# mattduino_mvp.net
KiCad netlist of a schematic drawn in EAGLE
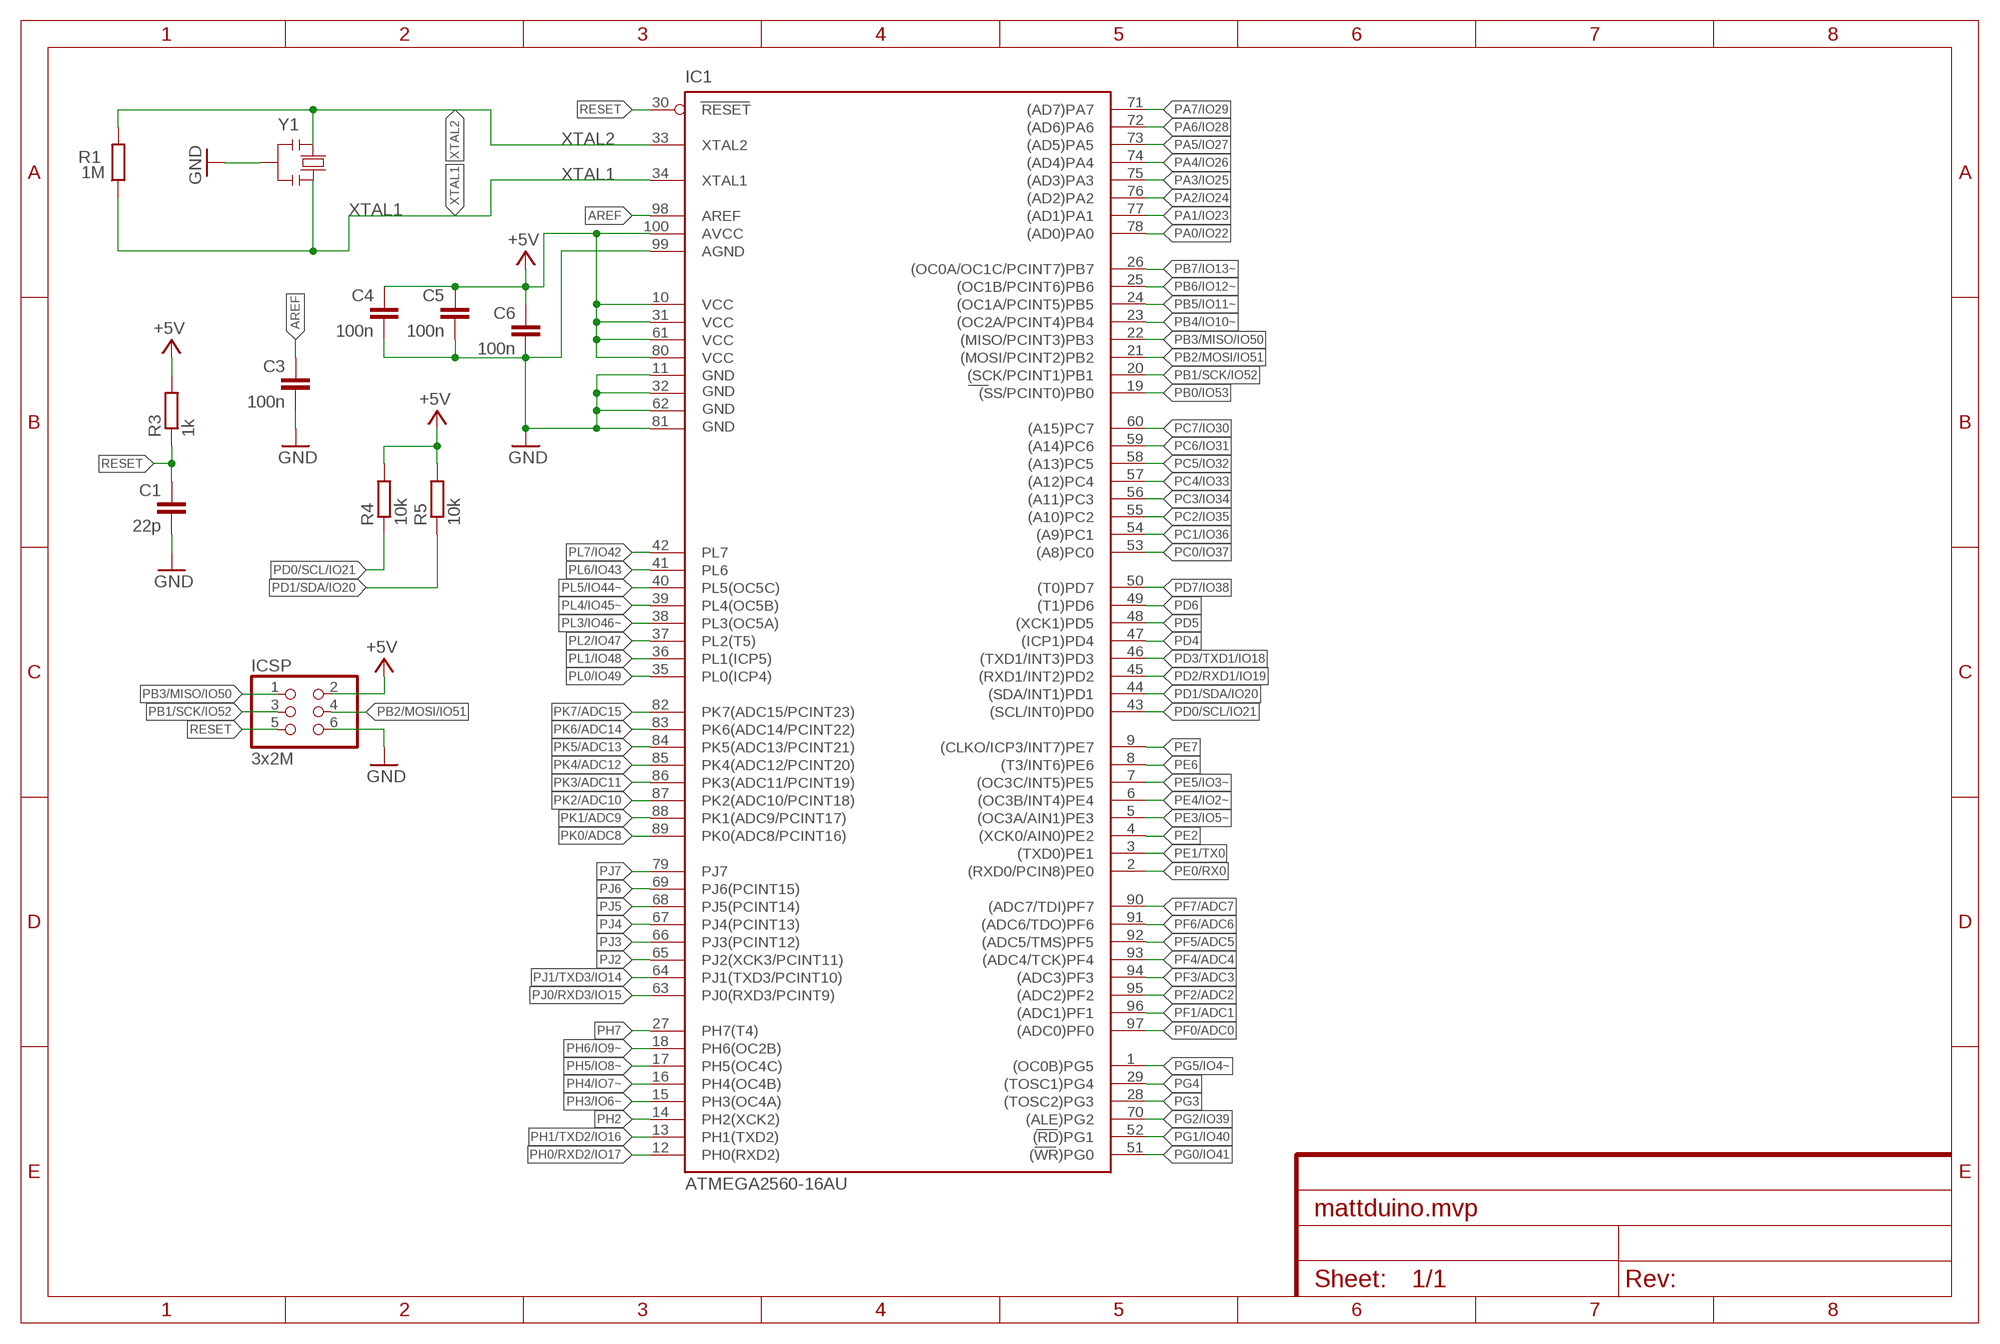
[diagram p0: schematic, sheet 1]

(export (version "E")
  (design (tool "Eeschema 10.0.6"))
  (components
    (comp (ref "C1")
      (value "22p")
      (footprint "eagle-import:C1206")
      (libsource (lib "eagle-import") (part "C-EUC1206"))
    )
    (comp (ref "C3")
      (value "100n")
      (footprint "eagle-import:C1206")
      (libsource (lib "eagle-import") (part "C-EUC1206"))
    )
    (comp (ref "C4")
      (value "100n")
      (footprint "eagle-import:C1206")
      (libsource (lib "eagle-import") (part "C-EUC1206"))
    )
    (comp (ref "C5")
      (value "100n")
      (footprint "eagle-import:C1206")
      (libsource (lib "eagle-import") (part "C-EUC1206"))
    )
    (comp (ref "C6")
      (value "100n")
      (footprint "eagle-import:C1206")
      (libsource (lib "eagle-import") (part "C-EUC1206"))
    )
    (comp (ref "IC1")
      (value "ATMEGA2560-16AU")
      (footprint "eagle-import:TQFP100")
      (libsource (lib "eagle-import") (part "ATMEGA2560AU2560-16"))
    )
    (comp (ref "ICSP")
      (value "3x2M")
      (footprint "eagle-import:2X03")
      (libsource (lib "eagle-import") (part "PINHD-2X3"))
    )
    (comp (ref "R1")
      (value "1M")
      (footprint "eagle-import:R1206")
      (libsource (lib "eagle-import") (part "R-EU_R1206"))
    )
    (comp (ref "R3")
      (value "1k")
      (footprint "eagle-import:R1206")
      (libsource (lib "eagle-import") (part "R-EU_R1206"))
    )
    (comp (ref "R4")
      (value "10k")
      (footprint "eagle-import:R1206")
      (libsource (lib "eagle-import") (part "R-EU_R1206"))
    )
    (comp (ref "R5")
      (value "10k")
      (footprint "eagle-import:R1206")
      (libsource (lib "eagle-import") (part "R-EU_R1206"))
    )
    (comp (ref "Y1")
      (value "CSTCE16M0V53-R0 16MHZ")
      (footprint "eagle-import:RESONATOR")
      (libsource (lib "eagle-import") (part "RESONATORMU"))
    )
  )
  (nets
    (net (code "1") (name "+5V") (class "Default")
      (node (ref "C4") (pin "1") (pinfunction "1_1") (pintype "passive"))
      (node (ref "C5") (pin "1") (pinfunction "1_1") (pintype "passive"))
      (node (ref "C6") (pin "1") (pinfunction "1_1") (pintype "passive"))
      (node (ref "IC1") (pin "10") (pinfunction "VCC_10") (pintype "power_in"))
      (node (ref "IC1") (pin "100") (pinfunction "AVCC_100") (pintype "power_in"))
      (node (ref "IC1") (pin "31") (pinfunction "VCC1_31") (pintype "power_in"))
      (node (ref "IC1") (pin "61") (pinfunction "VCC2_61") (pintype "power_in"))
      (node (ref "IC1") (pin "80") (pinfunction "VCC3_80") (pintype "power_in"))
      (node (ref "ICSP") (pin "2") (pinfunction "2_2") (pintype "passive"))
      (node (ref "R3") (pin "2") (pinfunction "2_2") (pintype "passive"))
      (node (ref "R4") (pin "2") (pinfunction "2_2") (pintype "passive"))
      (node (ref "R5") (pin "2") (pinfunction "2_2") (pintype "passive"))
    )
    (net (code "2") (name "/PB4{slash}IO10~{}") (class "Default")
      (node (ref "IC1") (pin "23") (pinfunction "(OC2A/PCINT4)PB4_23") (pintype "bidirectional"))
    )
    (net (code "3") (name "/PB5{slash}IO11~{}") (class "Default")
      (node (ref "IC1") (pin "24") (pinfunction "(OC1A/PCINT5)PB5_24") (pintype "bidirectional"))
    )
    (net (code "4") (name "/PB6{slash}IO12~{}") (class "Default")
      (node (ref "IC1") (pin "25") (pinfunction "(OC1B/PCINT6)PB6_25") (pintype "bidirectional"))
    )
    (net (code "5") (name "/PB7{slash}IO13~{}") (class "Default")
      (node (ref "IC1") (pin "26") (pinfunction "(OC0A/OC1C/PCINT7)PB7_26") (pintype "bidirectional"))
    )
    (net (code "6") (name "/PE3{slash}IO5~{}") (class "Default")
      (node (ref "IC1") (pin "5") (pinfunction "(OC3A/AIN1)PE3_5") (pintype "bidirectional"))
    )
    (net (code "7") (name "/PE4{slash}IO2~{}") (class "Default")
      (node (ref "IC1") (pin "6") (pinfunction "(OC3B/INT4)PE4_6") (pintype "bidirectional"))
    )
    (net (code "8") (name "/PE5{slash}IO3~{}") (class "Default")
      (node (ref "IC1") (pin "7") (pinfunction "(OC3C/INT5)PE5_7") (pintype "bidirectional"))
    )
    (net (code "9") (name "/PG5{slash}IO4~{}") (class "Default")
      (node (ref "IC1") (pin "1") (pinfunction "(OC0B)PG5_1") (pintype "bidirectional"))
    )
    (net (code "10") (name "/PH3{slash}IO6~{}") (class "Default")
      (node (ref "IC1") (pin "15") (pinfunction "PH3(OC4A)_15") (pintype "bidirectional"))
    )
    (net (code "11") (name "/PH4{slash}IO7~{}") (class "Default")
      (node (ref "IC1") (pin "16") (pinfunction "PH4(OC4B)_16") (pintype "bidirectional"))
    )
    (net (code "12") (name "/PH5{slash}IO8~{}") (class "Default")
      (node (ref "IC1") (pin "17") (pinfunction "PH5(OC4C)_17") (pintype "bidirectional"))
    )
    (net (code "13") (name "/PH6{slash}IO9~{}") (class "Default")
      (node (ref "IC1") (pin "18") (pinfunction "PH6(OC2B)_18") (pintype "bidirectional"))
    )
    (net (code "14") (name "/PL3{slash}IO46~{}") (class "Default")
      (node (ref "IC1") (pin "38") (pinfunction "PL3(OC5A)_38") (pintype "bidirectional"))
    )
    (net (code "15") (name "/PL4{slash}IO45~{}") (class "Default")
      (node (ref "IC1") (pin "39") (pinfunction "PL4(OC5B)_39") (pintype "bidirectional"))
    )
    (net (code "16") (name "/PL5{slash}IO44~{}") (class "Default")
      (node (ref "IC1") (pin "40") (pinfunction "PL5(OC5C)_40") (pintype "bidirectional"))
    )
    (net (code "17") (name "AREF") (class "Default")
      (node (ref "C3") (pin "1") (pinfunction "1_1") (pintype "passive"))
      (node (ref "IC1") (pin "98") (pinfunction "AREF_98") (pintype "bidirectional"))
    )
    (net (code "18") (name "GND") (class "Default")
      (node (ref "C1") (pin "2") (pinfunction "2_2") (pintype "passive"))
      (node (ref "C3") (pin "2") (pinfunction "2_2") (pintype "passive"))
      (node (ref "C4") (pin "2") (pinfunction "2_2") (pintype "passive"))
      (node (ref "C5") (pin "2") (pinfunction "2_2") (pintype "passive"))
      (node (ref "C6") (pin "2") (pinfunction "2_2") (pintype "passive"))
      (node (ref "IC1") (pin "11") (pinfunction "GND_11") (pintype "power_in"))
      (node (ref "IC1") (pin "32") (pinfunction "GND1_32") (pintype "power_in"))
      (node (ref "IC1") (pin "62") (pinfunction "GND2_62") (pintype "power_in"))
      (node (ref "IC1") (pin "81") (pinfunction "GND3_81") (pintype "power_in"))
      (node (ref "IC1") (pin "99") (pinfunction "AGND_99") (pintype "power_in"))
      (node (ref "ICSP") (pin "6") (pinfunction "6_6") (pintype "passive"))
      (node (ref "Y1") (pin "2") (pinfunction "2_2") (pintype "passive"))
    )
    (net (code "19") (name "PA0{slash}IO22") (class "Default")
      (node (ref "IC1") (pin "78") (pinfunction "(AD0)PA0_78") (pintype "bidirectional"))
    )
    (net (code "20") (name "PA1{slash}IO23") (class "Default")
      (node (ref "IC1") (pin "77") (pinfunction "(AD1)PA1_77") (pintype "bidirectional"))
    )
    (net (code "21") (name "PA2{slash}IO24") (class "Default")
      (node (ref "IC1") (pin "76") (pinfunction "(AD2)PA2_76") (pintype "bidirectional"))
    )
    (net (code "22") (name "PA3{slash}IO25") (class "Default")
      (node (ref "IC1") (pin "75") (pinfunction "(AD3)PA3_75") (pintype "bidirectional"))
    )
    (net (code "23") (name "PA4{slash}IO26") (class "Default")
      (node (ref "IC1") (pin "74") (pinfunction "(AD4)PA4_74") (pintype "bidirectional"))
    )
    (net (code "24") (name "PA5{slash}IO27") (class "Default")
      (node (ref "IC1") (pin "73") (pinfunction "(AD5)PA5_73") (pintype "bidirectional"))
    )
    (net (code "25") (name "PA6{slash}IO28") (class "Default")
      (node (ref "IC1") (pin "72") (pinfunction "(AD6)PA6_72") (pintype "bidirectional"))
    )
    (net (code "26") (name "PA7{slash}IO29") (class "Default")
      (node (ref "IC1") (pin "71") (pinfunction "(AD7)PA7_71") (pintype "bidirectional"))
    )
    (net (code "27") (name "PB0{slash}IO53") (class "Default")
      (node (ref "IC1") (pin "19") (pinfunction "(SS/PCINT0)PB0_19") (pintype "bidirectional"))
    )
    (net (code "28") (name "PB1{slash}SCK{slash}IO52") (class "Default")
      (node (ref "IC1") (pin "20") (pinfunction "(SCK/PCINT1)PB1_20") (pintype "bidirectional"))
      (node (ref "ICSP") (pin "3") (pinfunction "3_3") (pintype "passive"))
    )
    (net (code "29") (name "PB2{slash}MOSI{slash}IO51") (class "Default")
      (node (ref "IC1") (pin "21") (pinfunction "(MOSI/PCINT2)PB2_21") (pintype "bidirectional"))
      (node (ref "ICSP") (pin "4") (pinfunction "4_4") (pintype "passive"))
    )
    (net (code "30") (name "PB3{slash}MISO{slash}IO50") (class "Default")
      (node (ref "IC1") (pin "22") (pinfunction "(MISO/PCINT3)PB3_22") (pintype "bidirectional"))
      (node (ref "ICSP") (pin "1") (pinfunction "1_1") (pintype "passive"))
    )
    (net (code "31") (name "PC0{slash}IO37") (class "Default")
      (node (ref "IC1") (pin "53") (pinfunction "(A8)PC0_53") (pintype "bidirectional"))
    )
    (net (code "32") (name "PC1{slash}IO36") (class "Default")
      (node (ref "IC1") (pin "54") (pinfunction "(A9)PC1_54") (pintype "bidirectional"))
    )
    (net (code "33") (name "PC2{slash}IO35") (class "Default")
      (node (ref "IC1") (pin "55") (pinfunction "(A10)PC2_55") (pintype "bidirectional"))
    )
    (net (code "34") (name "PC3{slash}IO34") (class "Default")
      (node (ref "IC1") (pin "56") (pinfunction "(A11)PC3_56") (pintype "bidirectional"))
    )
    (net (code "35") (name "PC4{slash}IO33") (class "Default")
      (node (ref "IC1") (pin "57") (pinfunction "(A12)PC4_57") (pintype "bidirectional"))
    )
    (net (code "36") (name "PC5{slash}IO32") (class "Default")
      (node (ref "IC1") (pin "58") (pinfunction "(A13)PC5_58") (pintype "bidirectional"))
    )
    (net (code "37") (name "PC6{slash}IO31") (class "Default")
      (node (ref "IC1") (pin "59") (pinfunction "(A14)PC6_59") (pintype "bidirectional"))
    )
    (net (code "38") (name "PC7{slash}IO30") (class "Default")
      (node (ref "IC1") (pin "60") (pinfunction "(A15)PC7_60") (pintype "bidirectional"))
    )
    (net (code "39") (name "PD0{slash}SCL{slash}IO21") (class "Default")
      (node (ref "IC1") (pin "43") (pinfunction "(SCL/INT0)PD0_43") (pintype "bidirectional"))
      (node (ref "R4") (pin "1") (pinfunction "1_1") (pintype "passive"))
    )
    (net (code "40") (name "PD1{slash}SDA{slash}IO20") (class "Default")
      (node (ref "IC1") (pin "44") (pinfunction "(SDA/INT1)PD1_44") (pintype "bidirectional"))
      (node (ref "R5") (pin "1") (pinfunction "1_1") (pintype "passive"))
    )
    (net (code "41") (name "PD2{slash}RXD1{slash}IO19") (class "Default")
      (node (ref "IC1") (pin "45") (pinfunction "(RXD1/INT2)PD2_45") (pintype "bidirectional"))
    )
    (net (code "42") (name "PD3{slash}TXD1{slash}IO18") (class "Default")
      (node (ref "IC1") (pin "46") (pinfunction "(TXD1/INT3)PD3_46") (pintype "bidirectional"))
    )
    (net (code "43") (name "PD4") (class "Default")
      (node (ref "IC1") (pin "47") (pinfunction "(ICP1)PD4_47") (pintype "bidirectional"))
    )
    (net (code "44") (name "PD5") (class "Default")
      (node (ref "IC1") (pin "48") (pinfunction "(XCK1)PD5_48") (pintype "bidirectional"))
    )
    (net (code "45") (name "PD6") (class "Default")
      (node (ref "IC1") (pin "49") (pinfunction "(T1)PD6_49") (pintype "bidirectional"))
    )
    (net (code "46") (name "PD7{slash}IO38") (class "Default")
      (node (ref "IC1") (pin "50") (pinfunction "(T0)PD7_50") (pintype "bidirectional"))
    )
    (net (code "47") (name "PE0{slash}RX0") (class "Default")
      (node (ref "IC1") (pin "2") (pinfunction "(RXD0/PCIN8)PE0_2") (pintype "bidirectional"))
    )
    (net (code "48") (name "PE1{slash}TX0") (class "Default")
      (node (ref "IC1") (pin "3") (pinfunction "(TXD0)PE1_3") (pintype "bidirectional"))
    )
    (net (code "49") (name "PE2") (class "Default")
      (node (ref "IC1") (pin "4") (pinfunction "(XCK0/AIN0)PE2_4") (pintype "bidirectional"))
    )
    (net (code "50") (name "PE6") (class "Default")
      (node (ref "IC1") (pin "8") (pinfunction "(T3/INT6)PE6_8") (pintype "bidirectional"))
    )
    (net (code "51") (name "PE7") (class "Default")
      (node (ref "IC1") (pin "9") (pinfunction "(CLKO/ICP3/INT7)PE7_9") (pintype "bidirectional"))
    )
    (net (code "52") (name "PF0{slash}ADC0") (class "Default")
      (node (ref "IC1") (pin "97") (pinfunction "(ADC0)PF0_97") (pintype "bidirectional"))
    )
    (net (code "53") (name "PF1{slash}ADC1") (class "Default")
      (node (ref "IC1") (pin "96") (pinfunction "(ADC1)PF1_96") (pintype "bidirectional"))
    )
    (net (code "54") (name "PF2{slash}ADC2") (class "Default")
      (node (ref "IC1") (pin "95") (pinfunction "(ADC2)PF2_95") (pintype "bidirectional"))
    )
    (net (code "55") (name "PF3{slash}ADC3") (class "Default")
      (node (ref "IC1") (pin "94") (pinfunction "(ADC3)PF3_94") (pintype "bidirectional"))
    )
    (net (code "56") (name "PF4{slash}ADC4") (class "Default")
      (node (ref "IC1") (pin "93") (pinfunction "(ADC4/TCK)PF4_93") (pintype "bidirectional"))
    )
    (net (code "57") (name "PF5{slash}ADC5") (class "Default")
      (node (ref "IC1") (pin "92") (pinfunction "(ADC5/TMS)PF5_92") (pintype "bidirectional"))
    )
    (net (code "58") (name "PF6{slash}ADC6") (class "Default")
      (node (ref "IC1") (pin "91") (pinfunction "(ADC6/TDO)PF6_91") (pintype "bidirectional"))
    )
    (net (code "59") (name "PF7{slash}ADC7") (class "Default")
      (node (ref "IC1") (pin "90") (pinfunction "(ADC7/TDI)PF7_90") (pintype "bidirectional"))
    )
    (net (code "60") (name "PG0{slash}IO41") (class "Default")
      (node (ref "IC1") (pin "51") (pinfunction "(WR)PG0_51") (pintype "bidirectional"))
    )
    (net (code "61") (name "PG1{slash}IO40") (class "Default")
      (node (ref "IC1") (pin "52") (pinfunction "(RD)PG1_52") (pintype "bidirectional"))
    )
    (net (code "62") (name "PG2{slash}IO39") (class "Default")
      (node (ref "IC1") (pin "70") (pinfunction "(ALE)PG2_70") (pintype "bidirectional"))
    )
    (net (code "63") (name "PG3") (class "Default")
      (node (ref "IC1") (pin "28") (pinfunction "(TOSC2)PG3_28") (pintype "bidirectional"))
    )
    (net (code "64") (name "PG4") (class "Default")
      (node (ref "IC1") (pin "29") (pinfunction "(TOSC1)PG4_29") (pintype "bidirectional"))
    )
    (net (code "65") (name "PH0{slash}RXD2{slash}IO17") (class "Default")
      (node (ref "IC1") (pin "12") (pinfunction "PH0(RXD2)_12") (pintype "bidirectional"))
    )
    (net (code "66") (name "PH1{slash}TXD2{slash}IO16") (class "Default")
      (node (ref "IC1") (pin "13") (pinfunction "PH1(TXD2)_13") (pintype "bidirectional"))
    )
    (net (code "67") (name "PH2") (class "Default")
      (node (ref "IC1") (pin "14") (pinfunction "PH2(XCK2)_14") (pintype "bidirectional"))
    )
    (net (code "68") (name "PH7") (class "Default")
      (node (ref "IC1") (pin "27") (pinfunction "PH7(T4)_27") (pintype "bidirectional"))
    )
    (net (code "69") (name "PJ0{slash}RXD3{slash}IO15") (class "Default")
      (node (ref "IC1") (pin "63") (pinfunction "PJ0(RXD3/PCINT9)_63") (pintype "bidirectional"))
    )
    (net (code "70") (name "PJ1{slash}TXD3{slash}IO14") (class "Default")
      (node (ref "IC1") (pin "64") (pinfunction "PJ1(TXD3/PCINT10)_64") (pintype "bidirectional"))
    )
    (net (code "71") (name "PJ2") (class "Default")
      (node (ref "IC1") (pin "65") (pinfunction "PJ2(XCK3/PCINT11)_65") (pintype "bidirectional"))
    )
    (net (code "72") (name "PJ3") (class "Default")
      (node (ref "IC1") (pin "66") (pinfunction "PJ3(PCINT12)_66") (pintype "bidirectional"))
    )
    (net (code "73") (name "PJ4") (class "Default")
      (node (ref "IC1") (pin "67") (pinfunction "PJ4(PCINT13)_67") (pintype "bidirectional"))
    )
    (net (code "74") (name "PJ5") (class "Default")
      (node (ref "IC1") (pin "68") (pinfunction "PJ5(PCINT14)_68") (pintype "bidirectional"))
    )
    (net (code "75") (name "PJ6") (class "Default")
      (node (ref "IC1") (pin "69") (pinfunction "PJ6(PCINT15)_69") (pintype "bidirectional"))
    )
    (net (code "76") (name "PJ7") (class "Default")
      (node (ref "IC1") (pin "79") (pinfunction "PJ7_79") (pintype "bidirectional"))
    )
    (net (code "77") (name "PK0{slash}ADC8") (class "Default")
      (node (ref "IC1") (pin "89") (pinfunction "PK0(ADC8/PCINT16)_89") (pintype "bidirectional"))
    )
    (net (code "78") (name "PK1{slash}ADC9") (class "Default")
      (node (ref "IC1") (pin "88") (pinfunction "PK1(ADC9/PCINT17)_88") (pintype "bidirectional"))
    )
    (net (code "79") (name "PK2{slash}ADC10") (class "Default")
      (node (ref "IC1") (pin "87") (pinfunction "PK2(ADC10/PCINT18)_87") (pintype "bidirectional"))
    )
    (net (code "80") (name "PK3{slash}ADC11") (class "Default")
      (node (ref "IC1") (pin "86") (pinfunction "PK3(ADC11/PCINT19)_86") (pintype "bidirectional"))
    )
    (net (code "81") (name "PK4{slash}ADC12") (class "Default")
      (node (ref "IC1") (pin "85") (pinfunction "PK4(ADC12/PCINT20)_85") (pintype "bidirectional"))
    )
    (net (code "82") (name "PK5{slash}ADC13") (class "Default")
      (node (ref "IC1") (pin "84") (pinfunction "PK5(ADC13/PCINT21)_84") (pintype "bidirectional"))
    )
    (net (code "83") (name "PK6{slash}ADC14") (class "Default")
      (node (ref "IC1") (pin "83") (pinfunction "PK6(ADC14/PCINT22)_83") (pintype "bidirectional"))
    )
    (net (code "84") (name "PK7{slash}ADC15") (class "Default")
      (node (ref "IC1") (pin "82") (pinfunction "PK7(ADC15/PCINT23)_82") (pintype "bidirectional"))
    )
    (net (code "85") (name "PL0{slash}IO49") (class "Default")
      (node (ref "IC1") (pin "35") (pinfunction "PL0(ICP4)_35") (pintype "bidirectional"))
    )
    (net (code "86") (name "PL1{slash}IO48") (class "Default")
      (node (ref "IC1") (pin "36") (pinfunction "PL1(ICP5)_36") (pintype "bidirectional"))
    )
    (net (code "87") (name "PL2{slash}IO47") (class "Default")
      (node (ref "IC1") (pin "37") (pinfunction "PL2(T5)_37") (pintype "bidirectional"))
    )
    (net (code "88") (name "PL6{slash}IO43") (class "Default")
      (node (ref "IC1") (pin "41") (pinfunction "PL6_41") (pintype "bidirectional"))
    )
    (net (code "89") (name "PL7{slash}IO42") (class "Default")
      (node (ref "IC1") (pin "42") (pinfunction "PL7_42") (pintype "bidirectional"))
    )
    (net (code "90") (name "RESET") (class "Default")
      (node (ref "C1") (pin "1") (pinfunction "1_1") (pintype "passive"))
      (node (ref "IC1") (pin "30") (pinfunction "RESET_30") (pintype "input"))
      (node (ref "ICSP") (pin "5") (pinfunction "5_5") (pintype "passive"))
      (node (ref "R3") (pin "1") (pinfunction "1_1") (pintype "passive"))
    )
    (net (code "91") (name "XTAL1") (class "Default")
      (node (ref "IC1") (pin "34") (pinfunction "XTAL1_34") (pintype "input"))
      (node (ref "R1") (pin "1") (pinfunction "1_1") (pintype "passive"))
      (node (ref "Y1") (pin "3") (pinfunction "3_3") (pintype "passive"))
    )
    (net (code "92") (name "XTAL2") (class "Default")
      (node (ref "IC1") (pin "33") (pinfunction "XTAL2_33") (pintype "output"))
      (node (ref "R1") (pin "2") (pinfunction "2_2") (pintype "passive"))
      (node (ref "Y1") (pin "1") (pinfunction "1_1") (pintype "passive"))
    )
  )
)
